# Engine_Room_ADUM_v2_1.net
KiCad netlist of a schematic drawn in EAGLE
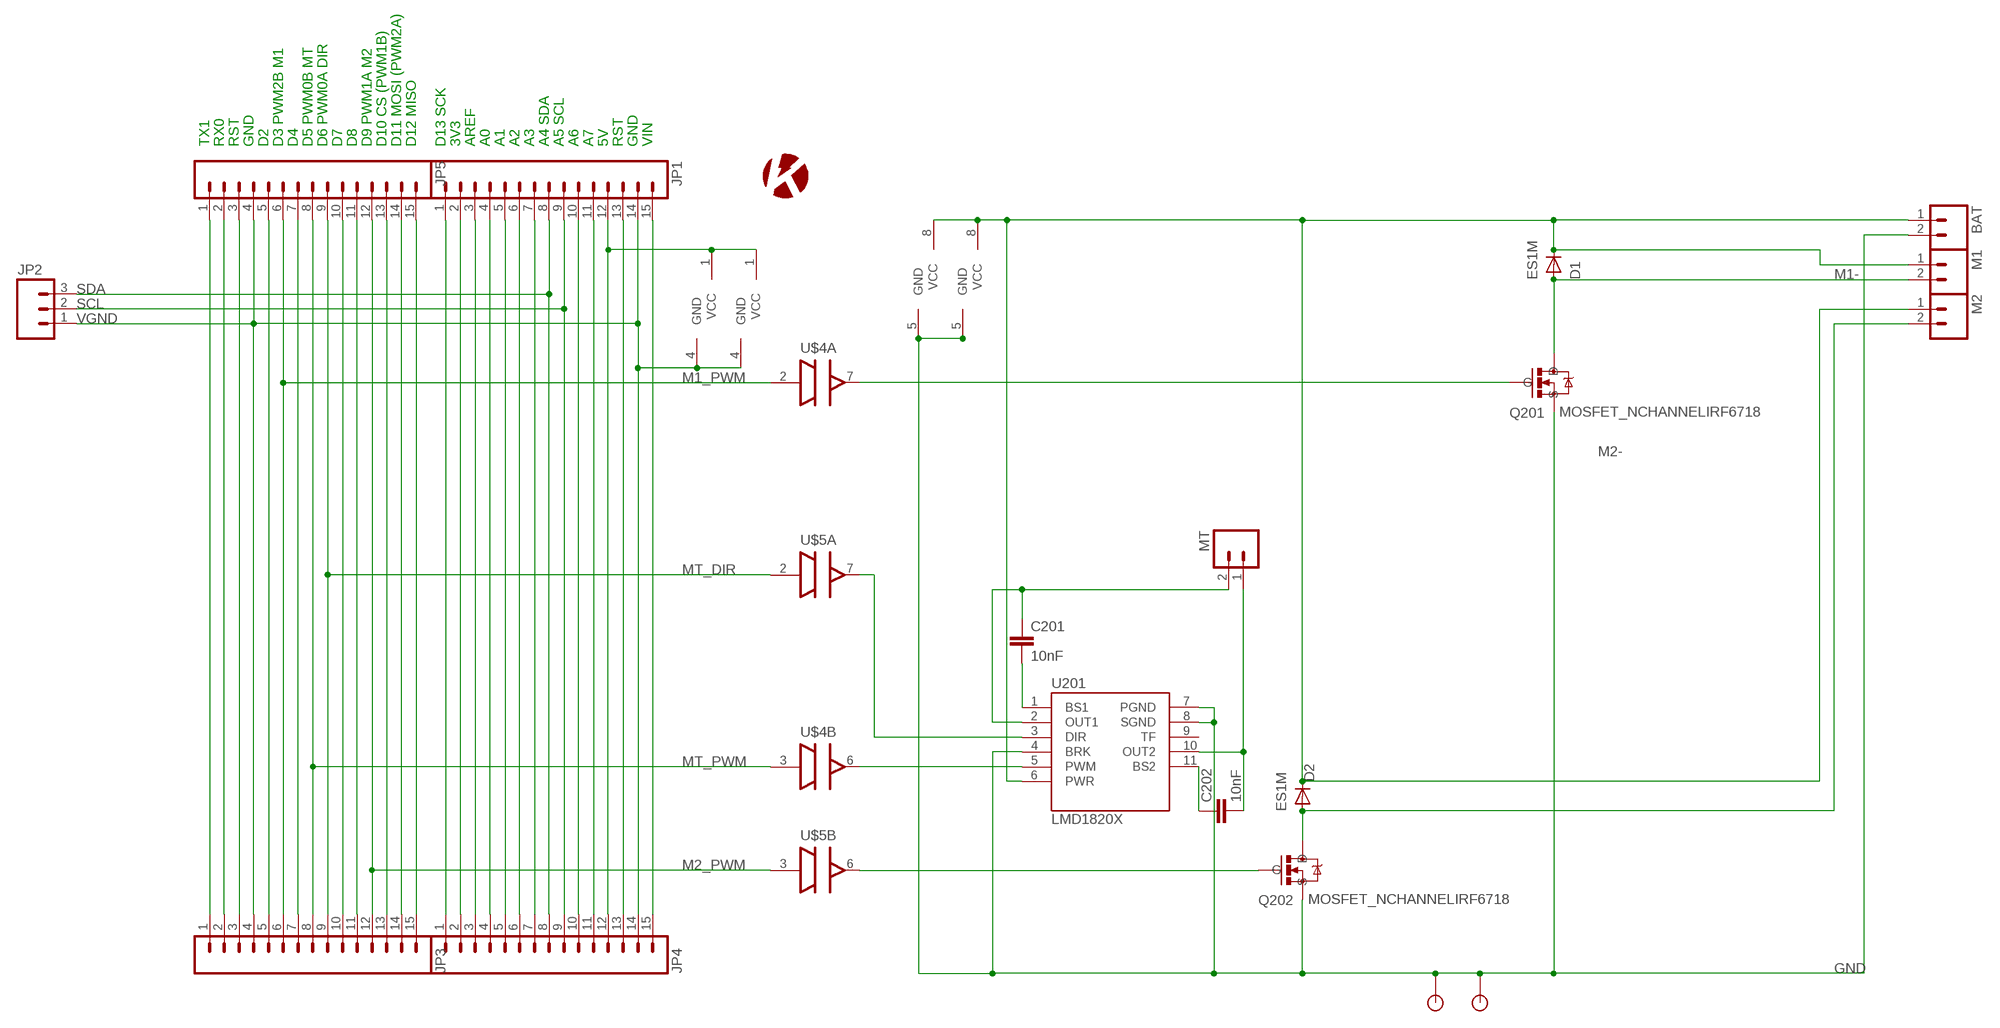
[diagram p0: schematic, sheet 1]

(export (version "E")
  (design (tool "Eeschema 10.0.6"))
  (components
    (comp (ref "BAT")
      (value "M02PTH4")
      (footprint "eagle-import:1X02_XTRA_BIG")
      (libsource (lib "eagle-import") (part "M02PTH4"))
    )
    (comp (ref "C201")
      (value "10nF")
      (footprint "eagle-import:0402-CAP")
      (libsource (lib "eagle-import") (part "CAP0402-CAP"))
    )
    (comp (ref "C202")
      (value "10nF")
      (footprint "eagle-import:0402-CAP")
      (libsource (lib "eagle-import") (part "CAP0402-CAP"))
    )
    (comp (ref "D1")
      (value "ES1M")
      (footprint "eagle-import:DO-214AC")
      (libsource (lib "eagle-import") (part "DIODE-DO-214AC"))
    )
    (comp (ref "D2")
      (value "ES1M")
      (footprint "eagle-import:DO-214AC")
      (libsource (lib "eagle-import") (part "DIODE-DO-214AC"))
    )
    (comp (ref "JP1")
      (value "M15")
      (footprint "eagle-import:1X15")
      (libsource (lib "eagle-import") (part "SparkFun-Connectors_M15"))
    )
    (comp (ref "JP2")
      (value "M03LOCK")
      (footprint "eagle-import:1X03_LOCK")
      (libsource (lib "eagle-import") (part "M03LOCK"))
    )
    (comp (ref "JP3")
      (value "M15")
      (footprint "eagle-import:1X15")
      (libsource (lib "eagle-import") (part "M15"))
    )
    (comp (ref "JP4")
      (value "M15")
      (footprint "eagle-import:1X15")
      (libsource (lib "eagle-import") (part "M15"))
    )
    (comp (ref "JP5")
      (value "M15")
      (footprint "eagle-import:1X15")
      (libsource (lib "eagle-import") (part "SparkFun-Connectors_M15"))
    )
    (comp (ref "M1")
      (value "M02PTH4")
      (footprint "eagle-import:1X02_XTRA_BIG")
      (libsource (lib "eagle-import") (part "M02PTH4"))
    )
    (comp (ref "M2")
      (value "M02PTH4")
      (footprint "eagle-import:1X02_XTRA_BIG")
      (libsource (lib "eagle-import") (part "M02PTH4"))
    )
    (comp (ref "MT")
      (value "M02PTH")
      (footprint "eagle-import:1X02")
      (libsource (lib "eagle-import") (part "M02PTH"))
    )
    (comp (ref "Q201")
      (value "MOSFET_NCHANNELIRF6718")
      (footprint "eagle-import:DIRECTFET_L6")
      (libsource (lib "eagle-import") (part "MOSFET_NCHANNELIRF6718"))
    )
    (comp (ref "Q202")
      (value "MOSFET_NCHANNELIRF6718")
      (footprint "eagle-import:DIRECTFET_L6")
      (libsource (lib "eagle-import") (part "MOSFET_NCHANNELIRF6718"))
    )
    (comp (ref "U$1")
      (value "KWAN_CIRCLE")
      (footprint "eagle-import:KWAN_CIRCLE")
      (libsource (lib "eagle-import") (part "KWAN_CIRCLE"))
    )
    (comp (ref "U$4")
      (value "ADUM3221")
      (footprint "eagle-import:SO8N")
      (libsource (lib "eagle-import") (part "ADUM3221"))
    )
    (comp (ref "U$5")
      (value "ADUM3221")
      (footprint "eagle-import:SO8N")
      (libsource (lib "eagle-import") (part "ADUM3221"))
    )
    (comp (ref "U$6")
      (value "STANDOFF")
      (footprint "eagle-import:STANDOFF")
      (libsource (lib "eagle-import") (part "STANDOFF"))
    )
    (comp (ref "U$7")
      (value "STANDOFF")
      (footprint "eagle-import:STANDOFF")
      (libsource (lib "eagle-import") (part "STANDOFF"))
    )
    (comp (ref "U201")
      (value "LMD1820X")
      (footprint "eagle-import:TO-220-11LEAD")
      (libsource (lib "eagle-import") (part "LMD1820X"))
    )
  )
  (nets
    (net (code "1") (name "/GND") (class "Default")
      (node (ref "BAT") (pin "2") (pinfunction "2_2") (pintype "passive"))
      (node (ref "Q201") (pin "S") (pinfunction "S_S") (pintype "passive"))
      (node (ref "Q202") (pin "S") (pinfunction "S_S") (pintype "passive"))
      (node (ref "U$4") (pin "5") (pinfunction "GND_5") (pintype "bidirectional"))
      (node (ref "U$5") (pin "5") (pinfunction "GND_5") (pintype "bidirectional"))
      (node (ref "U$6") (pin "P$1") (pinfunction "P$1_P$1") (pintype "bidirectional"))
      (node (ref "U$7") (pin "P$1") (pinfunction "P$1_P$1") (pintype "bidirectional"))
      (node (ref "U201") (pin "4") (pinfunction "BRK_4") (pintype "bidirectional"))
      (node (ref "U201") (pin "7") (pinfunction "PGND_7") (pintype "bidirectional"))
      (node (ref "U201") (pin "8") (pinfunction "SGND_8") (pintype "bidirectional"))
    )
    (net (code "2") (name "/M1-") (class "Default")
      (node (ref "D1") (pin "A") (pinfunction "A_A") (pintype "passive"))
      (node (ref "M1") (pin "2") (pinfunction "2_2") (pintype "passive"))
      (node (ref "Q201") (pin "D1") (pinfunction "D_D1") (pintype "passive"))
      (node (ref "Q201") (pin "D2") (pinfunction "D_D2") (pintype "passive"))
    )
    (net (code "3") (name "/M1_PWM") (class "Default")
      (node (ref "JP3") (pin "6") (pinfunction "6_6") (pintype "passive"))
      (node (ref "JP5") (pin "6") (pinfunction "6_6") (pintype "passive"))
      (node (ref "U$4") (pin "2") (pinfunction "IN_2") (pintype "input"))
    )
    (net (code "4") (name "/M2-") (class "Default")
      (node (ref "D2") (pin "A") (pinfunction "A_A") (pintype "passive"))
      (node (ref "M2") (pin "2") (pinfunction "2_2") (pintype "passive"))
      (node (ref "Q202") (pin "D1") (pinfunction "D_D1") (pintype "passive"))
      (node (ref "Q202") (pin "D2") (pinfunction "D_D2") (pintype "passive"))
    )
    (net (code "5") (name "/M2_PWM") (class "Default")
      (node (ref "JP3") (pin "12") (pinfunction "12_12") (pintype "passive"))
      (node (ref "JP5") (pin "12") (pinfunction "12_12") (pintype "passive"))
      (node (ref "U$5") (pin "3") (pinfunction "IN_3") (pintype "input"))
    )
    (net (code "6") (name "/MT_DIR") (class "Default")
      (node (ref "JP3") (pin "9") (pinfunction "9_9") (pintype "passive"))
      (node (ref "JP5") (pin "9") (pinfunction "9_9") (pintype "passive"))
      (node (ref "U$5") (pin "2") (pinfunction "IN_2") (pintype "input"))
    )
    (net (code "7") (name "/MT_PWM") (class "Default")
      (node (ref "JP3") (pin "8") (pinfunction "8_8") (pintype "passive"))
      (node (ref "JP5") (pin "8") (pinfunction "8_8") (pintype "passive"))
      (node (ref "U$4") (pin "3") (pinfunction "IN_3") (pintype "input"))
    )
    (net (code "8") (name "/SCL") (class "Default")
      (node (ref "JP1") (pin "9") (pinfunction "9_9") (pintype "passive"))
      (node (ref "JP2") (pin "2") (pinfunction "2_2") (pintype "passive"))
      (node (ref "JP4") (pin "9") (pinfunction "9_9") (pintype "passive"))
    )
    (net (code "9") (name "/SDA") (class "Default")
      (node (ref "JP1") (pin "8") (pinfunction "8_8") (pintype "passive"))
      (node (ref "JP2") (pin "3") (pinfunction "3_3") (pintype "passive"))
      (node (ref "JP4") (pin "8") (pinfunction "8_8") (pintype "passive"))
    )
    (net (code "10") (name "/VGND") (class "Default")
      (node (ref "JP1") (pin "14") (pinfunction "14_14") (pintype "passive"))
      (node (ref "JP2") (pin "1") (pinfunction "1_1") (pintype "passive"))
      (node (ref "JP3") (pin "4") (pinfunction "4_4") (pintype "passive"))
      (node (ref "JP4") (pin "14") (pinfunction "14_14") (pintype "passive"))
      (node (ref "JP5") (pin "4") (pinfunction "4_4") (pintype "passive"))
      (node (ref "U$4") (pin "4") (pinfunction "GND_4") (pintype "bidirectional"))
      (node (ref "U$5") (pin "4") (pinfunction "GND_4") (pintype "bidirectional"))
    )
    (net (code "11") (name "Net-(JP1-Pad1)") (class "Default")
      (node (ref "JP1") (pin "1") (pinfunction "1_1") (pintype "passive"))
      (node (ref "JP4") (pin "1") (pinfunction "1_1") (pintype "passive"))
    )
    (net (code "12") (name "Net-(JP1-Pad2)") (class "Default")
      (node (ref "JP1") (pin "2") (pinfunction "2_2") (pintype "passive"))
      (node (ref "JP4") (pin "2") (pinfunction "2_2") (pintype "passive"))
    )
    (net (code "13") (name "Net-(JP1-Pad3)") (class "Default")
      (node (ref "JP1") (pin "3") (pinfunction "3_3") (pintype "passive"))
      (node (ref "JP4") (pin "3") (pinfunction "3_3") (pintype "passive"))
    )
    (net (code "14") (name "Net-(JP1-Pad4)") (class "Default")
      (node (ref "JP1") (pin "4") (pinfunction "4_4") (pintype "passive"))
      (node (ref "JP4") (pin "4") (pinfunction "4_4") (pintype "passive"))
    )
    (net (code "15") (name "Net-(JP1-Pad5)") (class "Default")
      (node (ref "JP1") (pin "5") (pinfunction "5_5") (pintype "passive"))
      (node (ref "JP4") (pin "5") (pinfunction "5_5") (pintype "passive"))
    )
    (net (code "16") (name "Net-(JP1-Pad6)") (class "Default")
      (node (ref "JP1") (pin "6") (pinfunction "6_6") (pintype "passive"))
      (node (ref "JP4") (pin "6") (pinfunction "6_6") (pintype "passive"))
    )
    (net (code "17") (name "Net-(JP1-Pad7)") (class "Default")
      (node (ref "JP1") (pin "7") (pinfunction "7_7") (pintype "passive"))
      (node (ref "JP4") (pin "7") (pinfunction "7_7") (pintype "passive"))
    )
    (net (code "18") (name "Net-(JP1-Pad10)") (class "Default")
      (node (ref "JP1") (pin "10") (pinfunction "10_10") (pintype "passive"))
      (node (ref "JP4") (pin "10") (pinfunction "10_10") (pintype "passive"))
    )
    (net (code "19") (name "Net-(JP1-Pad11)") (class "Default")
      (node (ref "JP1") (pin "11") (pinfunction "11_11") (pintype "passive"))
      (node (ref "JP4") (pin "11") (pinfunction "11_11") (pintype "passive"))
    )
    (net (code "20") (name "Net-(JP1-Pad13)") (class "Default")
      (node (ref "JP1") (pin "13") (pinfunction "13_13") (pintype "passive"))
      (node (ref "JP4") (pin "13") (pinfunction "13_13") (pintype "passive"))
    )
    (net (code "21") (name "Net-(JP1-Pad15)") (class "Default")
      (node (ref "JP1") (pin "15") (pinfunction "15_15") (pintype "passive"))
      (node (ref "JP4") (pin "15") (pinfunction "15_15") (pintype "passive"))
    )
    (net (code "22") (name "Net-(JP3-Pad1)") (class "Default")
      (node (ref "JP3") (pin "1") (pinfunction "1_1") (pintype "passive"))
      (node (ref "JP5") (pin "1") (pinfunction "1_1") (pintype "passive"))
    )
    (net (code "23") (name "Net-(JP3-Pad2)") (class "Default")
      (node (ref "JP3") (pin "2") (pinfunction "2_2") (pintype "passive"))
      (node (ref "JP5") (pin "2") (pinfunction "2_2") (pintype "passive"))
    )
    (net (code "24") (name "Net-(JP3-Pad3)") (class "Default")
      (node (ref "JP3") (pin "3") (pinfunction "3_3") (pintype "passive"))
      (node (ref "JP5") (pin "3") (pinfunction "3_3") (pintype "passive"))
    )
    (net (code "25") (name "Net-(JP3-Pad5)") (class "Default")
      (node (ref "JP3") (pin "5") (pinfunction "5_5") (pintype "passive"))
      (node (ref "JP5") (pin "5") (pinfunction "5_5") (pintype "passive"))
    )
    (net (code "26") (name "Net-(JP3-Pad7)") (class "Default")
      (node (ref "JP3") (pin "7") (pinfunction "7_7") (pintype "passive"))
      (node (ref "JP5") (pin "7") (pinfunction "7_7") (pintype "passive"))
    )
    (net (code "27") (name "Net-(JP3-Pad10)") (class "Default")
      (node (ref "JP3") (pin "10") (pinfunction "10_10") (pintype "passive"))
      (node (ref "JP5") (pin "10") (pinfunction "10_10") (pintype "passive"))
    )
    (net (code "28") (name "Net-(JP3-Pad11)") (class "Default")
      (node (ref "JP3") (pin "11") (pinfunction "11_11") (pintype "passive"))
      (node (ref "JP5") (pin "11") (pinfunction "11_11") (pintype "passive"))
    )
    (net (code "29") (name "Net-(JP3-Pad13)") (class "Default")
      (node (ref "JP3") (pin "13") (pinfunction "13_13") (pintype "passive"))
      (node (ref "JP5") (pin "13") (pinfunction "13_13") (pintype "passive"))
    )
    (net (code "30") (name "Net-(JP3-Pad14)") (class "Default")
      (node (ref "JP3") (pin "14") (pinfunction "14_14") (pintype "passive"))
      (node (ref "JP5") (pin "14") (pinfunction "14_14") (pintype "passive"))
    )
    (net (code "31") (name "Net-(JP3-Pad15)") (class "Default")
      (node (ref "JP3") (pin "15") (pinfunction "15_15") (pintype "passive"))
      (node (ref "JP5") (pin "15") (pinfunction "15_15") (pintype "passive"))
    )
    (net (code "32") (name "Net-(U$4A-OUT)") (class "Default")
      (node (ref "Q201") (pin "G") (pinfunction "G_G") (pintype "passive"))
      (node (ref "U$4") (pin "7") (pinfunction "OUT_7") (pintype "bidirectional"))
    )
    (net (code "33") (name "Net-(U$4B-OUT)") (class "Default")
      (node (ref "U$4") (pin "6") (pinfunction "OUT_6") (pintype "bidirectional"))
      (node (ref "U201") (pin "5") (pinfunction "PWM_5") (pintype "bidirectional"))
    )
    (net (code "34") (name "Net-(U$4C-VCC)") (class "Default")
      (node (ref "JP1") (pin "12") (pinfunction "12_12") (pintype "passive"))
      (node (ref "JP4") (pin "12") (pinfunction "12_12") (pintype "passive"))
      (node (ref "U$4") (pin "1") (pinfunction "VCC_1") (pintype "bidirectional"))
      (node (ref "U$5") (pin "1") (pinfunction "VCC_1") (pintype "bidirectional"))
    )
    (net (code "35") (name "Net-(U$4D-VCC)") (class "Default")
      (node (ref "BAT") (pin "1") (pinfunction "1_1") (pintype "passive"))
      (node (ref "D1") (pin "C") (pinfunction "C_C") (pintype "passive"))
      (node (ref "D2") (pin "C") (pinfunction "C_C") (pintype "passive"))
      (node (ref "M1") (pin "1") (pinfunction "1_1") (pintype "passive"))
      (node (ref "M2") (pin "1") (pinfunction "1_1") (pintype "passive"))
      (node (ref "U$4") (pin "8") (pinfunction "VCC_8") (pintype "bidirectional"))
      (node (ref "U$5") (pin "8") (pinfunction "VCC_8") (pintype "bidirectional"))
      (node (ref "U201") (pin "6") (pinfunction "PWR_6") (pintype "bidirectional"))
    )
    (net (code "36") (name "Net-(U$5A-OUT)") (class "Default")
      (node (ref "U$5") (pin "7") (pinfunction "OUT_7") (pintype "bidirectional"))
      (node (ref "U201") (pin "3") (pinfunction "DIR_3") (pintype "bidirectional"))
    )
    (net (code "37") (name "Net-(U$5B-OUT)") (class "Default")
      (node (ref "Q202") (pin "G") (pinfunction "G_G") (pintype "passive"))
      (node (ref "U$5") (pin "6") (pinfunction "OUT_6") (pintype "bidirectional"))
    )
    (net (code "38") (name "Net-(U201-BS1)") (class "Default")
      (node (ref "C201") (pin "2") (pinfunction "2_2") (pintype "passive"))
      (node (ref "U201") (pin "1") (pinfunction "BS1_1") (pintype "bidirectional"))
    )
    (net (code "39") (name "Net-(U201-BS2)") (class "Default")
      (node (ref "C202") (pin "1") (pinfunction "1_1") (pintype "passive"))
      (node (ref "U201") (pin "11") (pinfunction "BS2_11") (pintype "bidirectional"))
    )
    (net (code "40") (name "Net-(U201-OUT1)") (class "Default")
      (node (ref "C201") (pin "1") (pinfunction "1_1") (pintype "passive"))
      (node (ref "MT") (pin "2") (pinfunction "2_2") (pintype "passive"))
      (node (ref "U201") (pin "2") (pinfunction "OUT1_2") (pintype "bidirectional"))
    )
    (net (code "41") (name "Net-(U201-OUT2)") (class "Default")
      (node (ref "C202") (pin "2") (pinfunction "2_2") (pintype "passive"))
      (node (ref "MT") (pin "1") (pinfunction "1_1") (pintype "passive"))
      (node (ref "U201") (pin "10") (pinfunction "OUT2_10") (pintype "bidirectional"))
    )
    (net (code "42") (name "unconnected-(U201-TF-Pad9)") (class "Default")
      (node (ref "U201") (pin "9") (pinfunction "TF_9") (pintype "bidirectional"))
    )
  )
)
